# Blink_Blink_Beep_Boop.net
KiCad netlist of a schematic drawn in Altium Designer
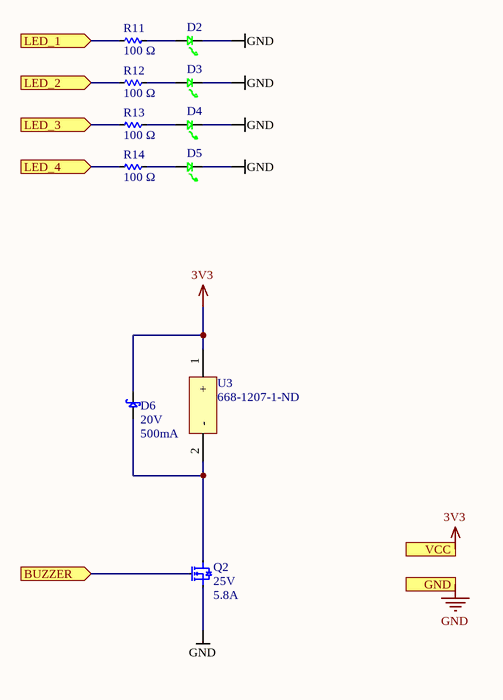
[diagram p0: Blink_Blink_Beep_Boop.SchDoc]

(export (version "E")
  (design (tool "Eeschema 10.0.6"))
  (components
    (comp (ref "D2")
      (value "LED_LY971")
      (footprint "0805_Diode")
      (description "LED 0805 GREEN 20MA")
      (fields
        (field (name "MANUFACTURER") "OSRAM Opto Semiconductors Inc")
        (field (name "MANUFACTURER PART NUMBER") "LG R971-KN-1")
      )
      (libsource (lib "SSI") (part "LED_LY971"))
    )
    (comp (ref "D3")
      (value "LED_LY971")
      (footprint "0805_Diode")
      (description "LED 0805 GREEN 20MA")
      (fields
        (field (name "MANUFACTURER") "OSRAM Opto Semiconductors Inc")
        (field (name "MANUFACTURER PART NUMBER") "LG R971-KN-1")
      )
      (libsource (lib "SSI") (part "LED_LY971"))
    )
    (comp (ref "D4")
      (value "LED_LY971")
      (footprint "0805_Diode")
      (description "LED 0805 GREEN 20MA")
      (fields
        (field (name "MANUFACTURER") "OSRAM Opto Semiconductors Inc")
        (field (name "MANUFACTURER PART NUMBER") "LG R971-KN-1")
      )
      (libsource (lib "SSI") (part "LED_LY971"))
    )
    (comp (ref "D5")
      (value "LED_LY971")
      (footprint "0805_Diode")
      (description "LED 0805 GREEN 20MA")
      (fields
        (field (name "MANUFACTURER") "OSRAM Opto Semiconductors Inc")
        (field (name "MANUFACTURER PART NUMBER") "LG R971-KN-1")
      )
      (libsource (lib "SSI") (part "LED_LY971"))
    )
    (comp (ref "D6")
      (value "SCHOTTKY_MBR0520L")
      (footprint "SOD123")
      (description "DIODE SCHOTTKY 0.5A 20V SOD-123")
      (fields
        (field (name "MANUFACTURER") "Fairchild Semiconductor")
        (field (name "MANUFACTURER PART NUMBER") "MBR0520L")
        (field (name "VOLTAGE - DC REVERSE (VR) (MAX)") "20V")
        (field (name "CURRENT - AVERAGE RECTIFIED (IO)") "500mA")
      )
      (libsource (lib "SSI") (part "SCHOTTKY_MBR0520L"))
    )
    (comp (ref "Q2")
      (value "NFET_IRFML8244TRPBF")
      (footprint "3SOT23")
      (description "MOSFET N-CH 25V 5.8A SOT23")
      (fields
        (field (name "MANUFACTURER") "International Rectifier")
        (field (name "MANUFACTURER PART NUMBER") "IRFML8244TRPBF")
        (field (name "DRAIN TO SOURCE VOLTAGE (VDSS)") "25V")
        (field (name "CURRENT - CONTINUOUS DRAIN (ID) @ 25° C") "5.8A")
      )
      (libsource (lib "SSI") (part "NFET_IRFML8244TRPBF"))
    )
    (comp (ref "R11")
      (value "__template_resistor")
      (footprint "R0603")
      (description "RES SMD 100 OHM 1% 1/10W 0603")
      (fields
        (field (name "MANUFACTURER PART NUMBER") "RC0603FR-07100RL")
        (field (name "MANUFACTURER") "Yageo")
        (field (name "RESISTANCE") "100 Ω")
      )
      (libsource (lib "passives") (part "__template_resistor"))
    )
    (comp (ref "R12")
      (value "__template_resistor")
      (footprint "R0603")
      (description "RES SMD 100 OHM 1% 1/10W 0603")
      (fields
        (field (name "MANUFACTURER PART NUMBER") "RC0603FR-07100RL")
        (field (name "MANUFACTURER") "Yageo")
        (field (name "RESISTANCE") "100 Ω")
      )
      (libsource (lib "passives") (part "__template_resistor"))
    )
    (comp (ref "R13")
      (value "__template_resistor")
      (footprint "R0603")
      (description "RES SMD 100 OHM 1% 1/10W 0603")
      (fields
        (field (name "MANUFACTURER PART NUMBER") "RC0603FR-07100RL")
        (field (name "MANUFACTURER") "Yageo")
        (field (name "RESISTANCE") "100 Ω")
      )
      (libsource (lib "passives") (part "__template_resistor"))
    )
    (comp (ref "R14")
      (value "__template_resistor")
      (footprint "R0603")
      (description "RES SMD 100 OHM 1% 1/10W 0603")
      (fields
        (field (name "MANUFACTURER PART NUMBER") "RC0603FR-07100RL")
        (field (name "MANUFACTURER") "Yageo")
        (field (name "RESISTANCE") "100 Ω")
      )
      (libsource (lib "passives") (part "__template_resistor"))
    )
    (comp (ref "U3")
      (value "BUZ_SMT-0540-T-7-R")
      (footprint "BUZ_SMT-0540-T-7-R")
      (description "Peak-Peak Signal Buzzer Single Tone 4kHz Magnetic 2 ~ 4V 78dB @ 3V, 10cm")
      (fields
        (field (name "MANUFACTURER") "PUI Audio, Inc.")
        (field (name "MANUFACTURER PART NUMBER") "SMT-0540-T-7-R")
        (field (name "SUPPLIER PART NUMBER 1") "668-1207-1-ND")
      )
      (libsource (lib "SSI") (part "BUZ_SMT-0540-T-7-R"))
    )
  )
  (nets
    (net (code "1") (name "/BUZZER") (class "Default") (node (ref "Q2") (pin "1") (pintype "passive")))
    (net (code "2") (name "/LED_1") (class "Default") (node (ref "R11") (pin "1") (pintype "passive")))
    (net (code "3") (name "/LED_2") (class "Default") (node (ref "R12") (pin "1") (pintype "passive")))
    (net (code "4") (name "/LED_3") (class "Default") (node (ref "R13") (pin "1") (pintype "passive")))
    (net (code "5") (name "/LED_4") (class "Default") (node (ref "R14") (pin "1") (pintype "passive")))
    (net (code "6") (name "3V3") (class "Default")
      (node (ref "D6") (pin "2") (pintype "passive"))
      (node (ref "U3") (pin "1") (pinfunction "+_1") (pintype "passive"))
    )
    (net (code "7") (name "GND") (class "Default")
      (node (ref "D2") (pin "1") (pintype "passive"))
      (node (ref "D3") (pin "1") (pintype "passive"))
      (node (ref "D4") (pin "1") (pintype "passive"))
      (node (ref "D5") (pin "1") (pintype "passive"))
      (node (ref "Q2") (pin "2") (pintype "passive"))
    )
    (net (code "8") (name "Net-(D2-Pad2)") (class "Default")
      (node (ref "D2") (pin "2") (pintype "passive"))
      (node (ref "R11") (pin "2") (pintype "passive"))
    )
    (net (code "9") (name "Net-(D3-Pad2)") (class "Default")
      (node (ref "D3") (pin "2") (pintype "passive"))
      (node (ref "R12") (pin "2") (pintype "passive"))
    )
    (net (code "10") (name "Net-(D4-Pad2)") (class "Default")
      (node (ref "D4") (pin "2") (pintype "passive"))
      (node (ref "R13") (pin "2") (pintype "passive"))
    )
    (net (code "11") (name "Net-(D5-Pad2)") (class "Default")
      (node (ref "D5") (pin "2") (pintype "passive"))
      (node (ref "R14") (pin "2") (pintype "passive"))
    )
    (net (code "12") (name "Net-(U3--)") (class "Default")
      (node (ref "D6") (pin "1") (pintype "passive"))
      (node (ref "Q2") (pin "3") (pintype "passive"))
      (node (ref "U3") (pin "2") (pinfunction "-_2") (pintype "passive"))
    )
  )
)
